# 7segement4digits1badidea-mk-4_2-smd.net
KiCad netlist of a schematic drawn in EAGLE
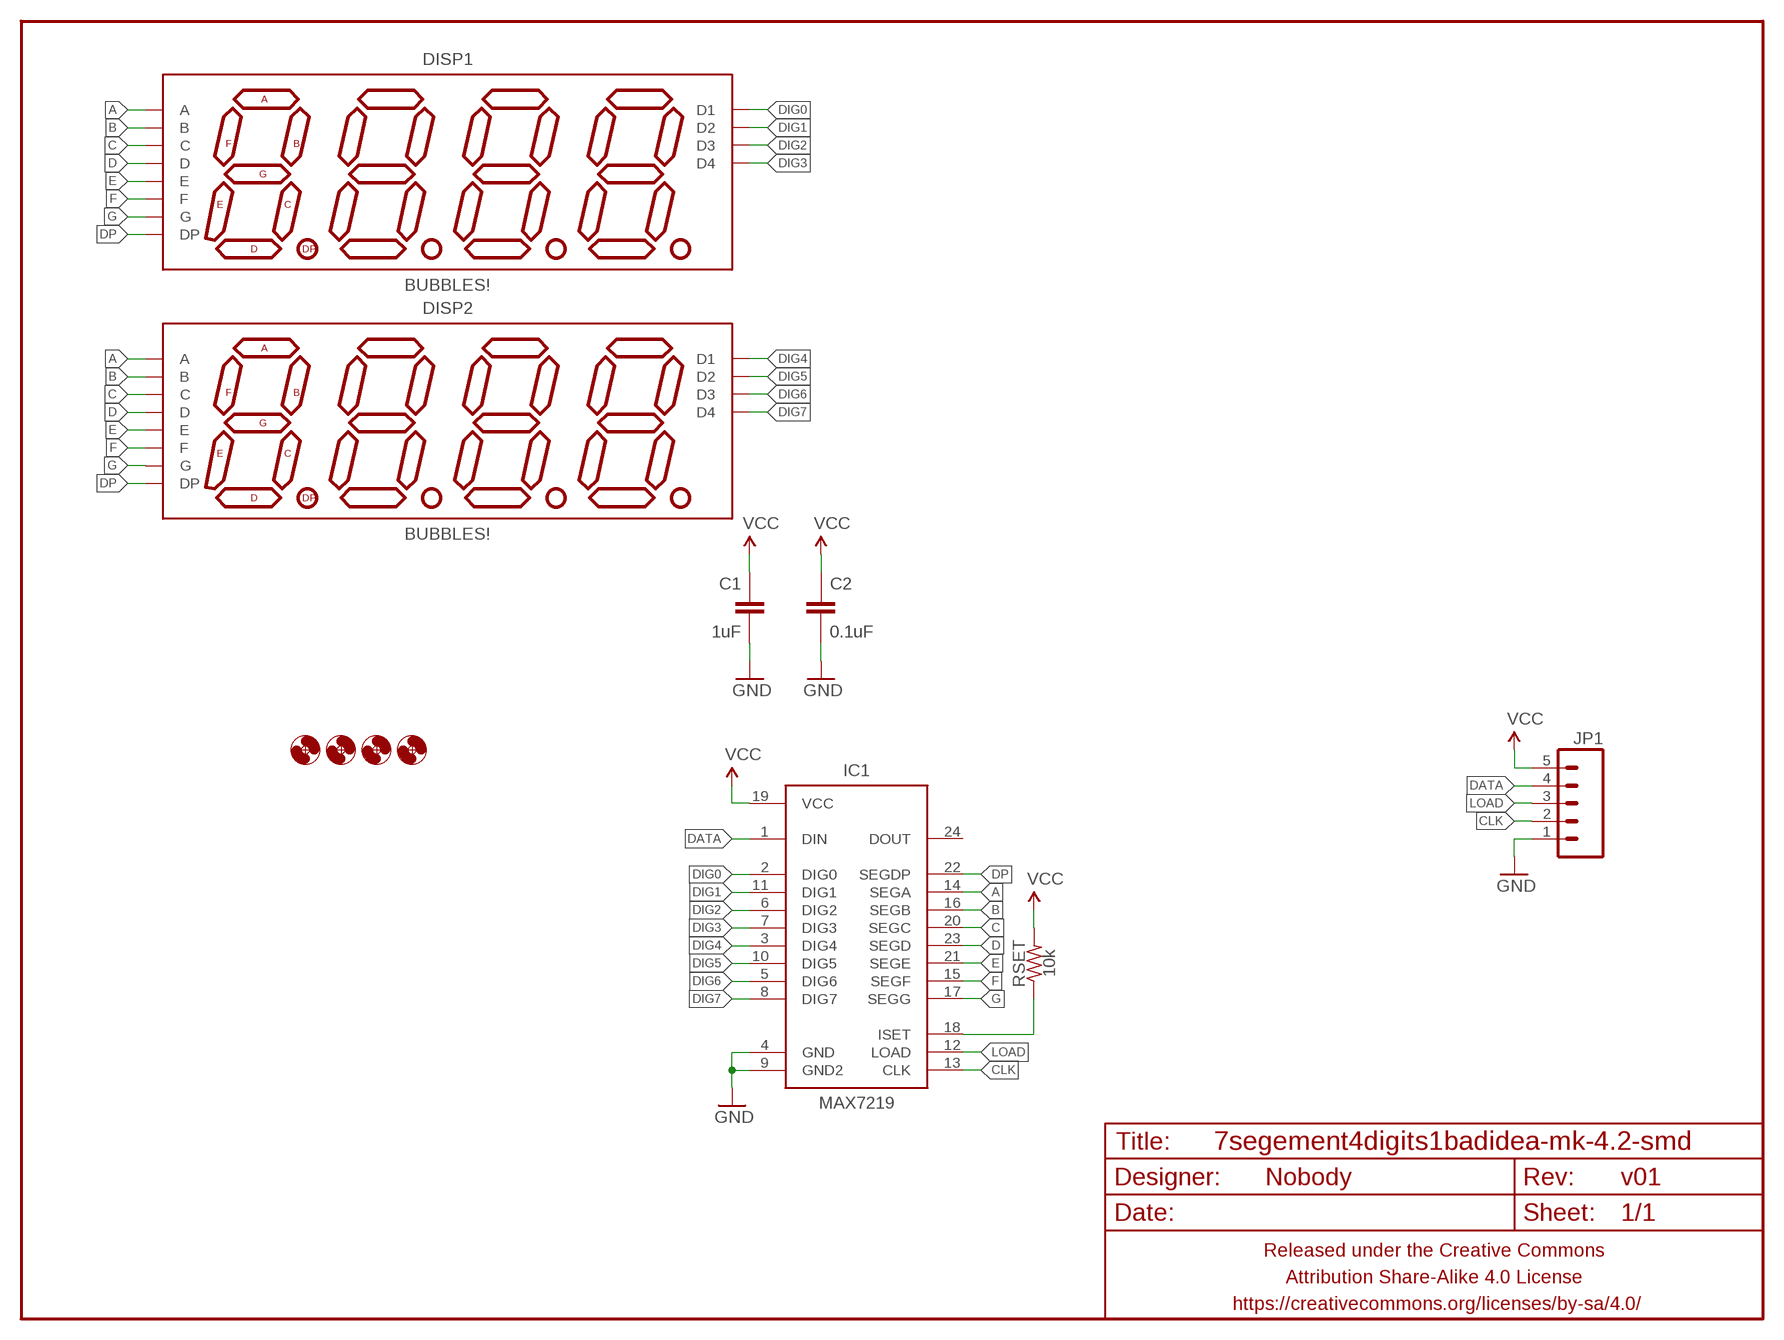
[diagram p0: schematic, sheet 1]

(export (version "E")
  (design (tool "Eeschema 10.0.6"))
  (components
    (comp (ref "C1")
      (value "1uF")
      (footprint "eagle-import:C025-024X044")
      (libsource (lib "eagle-import") (part "CAPACITOR-CERAMIC025-024X044"))
    )
    (comp (ref "C2")
      (value "0.1uF")
      (footprint "eagle-import:C025-024X044")
      (libsource (lib "eagle-import") (part "CAPACITOR-CERAMIC025-024X044"))
    )
    (comp (ref "DISP1")
      (value "BUBBLES!")
      (footprint "eagle-import:DIL12")
      (libsource (lib "eagle-import") (part "7SEG_4DIGITHP-BUBBLE"))
    )
    (comp (ref "DISP2")
      (value "BUBBLES!")
      (footprint "eagle-import:DIL12")
      (libsource (lib "eagle-import") (part "7SEG_4DIGITHP-BUBBLE"))
    )
    (comp (ref "FRAME1")
      (value "FRAME-LETTERNO_PACKAGE")
      (footprint "eagle-import:DUMMY")
      (fields (field (name "DESIGNER") "Nobody"))
      (libsource (lib "eagle-import") (part "FRAME-LETTERNO_PACKAGE"))
    )
    (comp (ref "H1")
      (value "HOLE#2")
      (footprint "eagle-import:HOLE-#2")
      (libsource (lib "eagle-import") (part "HOLE#2"))
    )
    (comp (ref "H2")
      (value "HOLE#2")
      (footprint "eagle-import:HOLE-#2")
      (libsource (lib "eagle-import") (part "HOLE#2"))
    )
    (comp (ref "H3")
      (value "HOLE#2")
      (footprint "eagle-import:HOLE-#2")
      (libsource (lib "eagle-import") (part "HOLE#2"))
    )
    (comp (ref "H4")
      (value "HOLE#2")
      (footprint "eagle-import:HOLE-#2")
      (libsource (lib "eagle-import") (part "HOLE#2"))
    )
    (comp (ref "IC1")
      (value "MAX7219")
      (footprint "eagle-import:SO24W")
      (libsource (lib "eagle-import") (part "MAX7219SOIC-W"))
    )
    (comp (ref "JP1")
      (value "M05PTH")
      (footprint "eagle-import:1X05")
      (libsource (lib "eagle-import") (part "M05PTH"))
    )
    (comp (ref "RSET")
      (value "10k")
      (footprint "eagle-import:RESISTOR-AXIAL-PTH-6.35MM")
      (libsource (lib "eagle-import") (part "RESISTORPTH-AXIAL-6.35MM"))
    )
  )
  (nets
    (net (code "1") (name "A") (class "Default")
      (node (ref "DISP1") (pin "12") (pinfunction "A_12") (pintype "bidirectional"))
      (node (ref "DISP2") (pin "12") (pinfunction "A_12") (pintype "bidirectional"))
      (node (ref "IC1") (pin "14") (pinfunction "SEGA_14") (pintype "bidirectional"))
    )
    (net (code "2") (name "B") (class "Default")
      (node (ref "DISP1") (pin "11") (pinfunction "B_11") (pintype "bidirectional"))
      (node (ref "DISP2") (pin "11") (pinfunction "B_11") (pintype "bidirectional"))
      (node (ref "IC1") (pin "16") (pinfunction "SEGB_16") (pintype "bidirectional"))
    )
    (net (code "3") (name "C") (class "Default")
      (node (ref "DISP1") (pin "3") (pinfunction "C_3") (pintype "bidirectional"))
      (node (ref "DISP2") (pin "3") (pinfunction "C_3") (pintype "bidirectional"))
      (node (ref "IC1") (pin "20") (pinfunction "SEGC_20") (pintype "bidirectional"))
    )
    (net (code "4") (name "CLK") (class "Default")
      (node (ref "IC1") (pin "13") (pinfunction "CLK_13") (pintype "bidirectional"))
      (node (ref "JP1") (pin "2") (pinfunction "2_2") (pintype "passive"))
    )
    (net (code "5") (name "D") (class "Default")
      (node (ref "DISP1") (pin "8") (pinfunction "D_8") (pintype "bidirectional"))
      (node (ref "DISP2") (pin "8") (pinfunction "D_8") (pintype "bidirectional"))
      (node (ref "IC1") (pin "23") (pinfunction "SEGD_23") (pintype "bidirectional"))
    )
    (net (code "6") (name "DATA") (class "Default")
      (node (ref "IC1") (pin "1") (pinfunction "DIN_1") (pintype "bidirectional"))
      (node (ref "JP1") (pin "4") (pinfunction "4_4") (pintype "passive"))
    )
    (net (code "7") (name "DIG0") (class "Default")
      (node (ref "DISP1") (pin "1") (pinfunction "D1_1") (pintype "bidirectional"))
      (node (ref "IC1") (pin "2") (pinfunction "DIG0_2") (pintype "bidirectional"))
    )
    (net (code "8") (name "DIG1") (class "Default")
      (node (ref "DISP1") (pin "10") (pinfunction "D2_10") (pintype "bidirectional"))
      (node (ref "IC1") (pin "11") (pinfunction "DIG1_11") (pintype "bidirectional"))
    )
    (net (code "9") (name "DIG2") (class "Default")
      (node (ref "DISP1") (pin "4") (pinfunction "D3_4") (pintype "bidirectional"))
      (node (ref "IC1") (pin "6") (pinfunction "DIG2_6") (pintype "bidirectional"))
    )
    (net (code "10") (name "DIG3") (class "Default")
      (node (ref "DISP1") (pin "6") (pinfunction "D4_6") (pintype "bidirectional"))
      (node (ref "IC1") (pin "7") (pinfunction "DIG3_7") (pintype "bidirectional"))
    )
    (net (code "11") (name "DIG4") (class "Default")
      (node (ref "DISP2") (pin "1") (pinfunction "D1_1") (pintype "bidirectional"))
      (node (ref "IC1") (pin "3") (pinfunction "DIG4_3") (pintype "bidirectional"))
    )
    (net (code "12") (name "DIG5") (class "Default")
      (node (ref "DISP2") (pin "10") (pinfunction "D2_10") (pintype "bidirectional"))
      (node (ref "IC1") (pin "10") (pinfunction "DIG5_10") (pintype "bidirectional"))
    )
    (net (code "13") (name "DIG6") (class "Default")
      (node (ref "DISP2") (pin "4") (pinfunction "D3_4") (pintype "bidirectional"))
      (node (ref "IC1") (pin "5") (pinfunction "DIG6_5") (pintype "bidirectional"))
    )
    (net (code "14") (name "DIG7") (class "Default")
      (node (ref "DISP2") (pin "6") (pinfunction "D4_6") (pintype "bidirectional"))
      (node (ref "IC1") (pin "8") (pinfunction "DIG7_8") (pintype "bidirectional"))
    )
    (net (code "15") (name "DP") (class "Default")
      (node (ref "DISP1") (pin "5") (pinfunction "DP_5") (pintype "bidirectional"))
      (node (ref "DISP2") (pin "5") (pinfunction "DP_5") (pintype "bidirectional"))
      (node (ref "IC1") (pin "22") (pinfunction "SEGDP_22") (pintype "bidirectional"))
    )
    (net (code "16") (name "E") (class "Default")
      (node (ref "DISP1") (pin "2") (pinfunction "E_2") (pintype "bidirectional"))
      (node (ref "DISP2") (pin "2") (pinfunction "E_2") (pintype "bidirectional"))
      (node (ref "IC1") (pin "21") (pinfunction "SEGE_21") (pintype "bidirectional"))
    )
    (net (code "17") (name "F") (class "Default")
      (node (ref "DISP1") (pin "9") (pinfunction "F_9") (pintype "bidirectional"))
      (node (ref "DISP2") (pin "9") (pinfunction "F_9") (pintype "bidirectional"))
      (node (ref "IC1") (pin "15") (pinfunction "SEGF_15") (pintype "bidirectional"))
    )
    (net (code "18") (name "G") (class "Default")
      (node (ref "DISP1") (pin "7") (pinfunction "G_7") (pintype "bidirectional"))
      (node (ref "DISP2") (pin "7") (pinfunction "G_7") (pintype "bidirectional"))
      (node (ref "IC1") (pin "17") (pinfunction "SEGG_17") (pintype "bidirectional"))
    )
    (net (code "19") (name "GND") (class "Default")
      (node (ref "C1") (pin "2") (pinfunction "2_2") (pintype "passive"))
      (node (ref "C2") (pin "2") (pinfunction "2_2") (pintype "passive"))
      (node (ref "IC1") (pin "4") (pinfunction "GND_4") (pintype "bidirectional"))
      (node (ref "IC1") (pin "9") (pinfunction "GND2_9") (pintype "bidirectional"))
      (node (ref "JP1") (pin "1") (pinfunction "1_1") (pintype "passive"))
    )
    (net (code "20") (name "LOAD") (class "Default")
      (node (ref "IC1") (pin "12") (pinfunction "LOAD_12") (pintype "bidirectional"))
      (node (ref "JP1") (pin "3") (pinfunction "3_3") (pintype "passive"))
    )
    (net (code "21") (name "Net-(IC1-ISET)") (class "Default")
      (node (ref "IC1") (pin "18") (pinfunction "ISET_18") (pintype "bidirectional"))
      (node (ref "RSET") (pin "P$1") (pinfunction "1_P$1") (pintype "passive"))
    )
    (net (code "22") (name "VCC") (class "Default")
      (node (ref "C1") (pin "1") (pinfunction "1_1") (pintype "passive"))
      (node (ref "C2") (pin "1") (pinfunction "1_1") (pintype "passive"))
      (node (ref "IC1") (pin "19") (pinfunction "VCC_19") (pintype "bidirectional"))
      (node (ref "JP1") (pin "5") (pinfunction "5_5") (pintype "passive"))
      (node (ref "RSET") (pin "P$2") (pinfunction "2_P$2") (pintype "passive"))
    )
    (net (code "23") (name "unconnected-(IC1-DOUT-Pad24)") (class "Default")
      (node (ref "IC1") (pin "24") (pinfunction "DOUT_24") (pintype "bidirectional"))
    )
  )
)
